# XIAO-HAT-3.net
KiCad netlist of a schematic drawn in Altium Designer
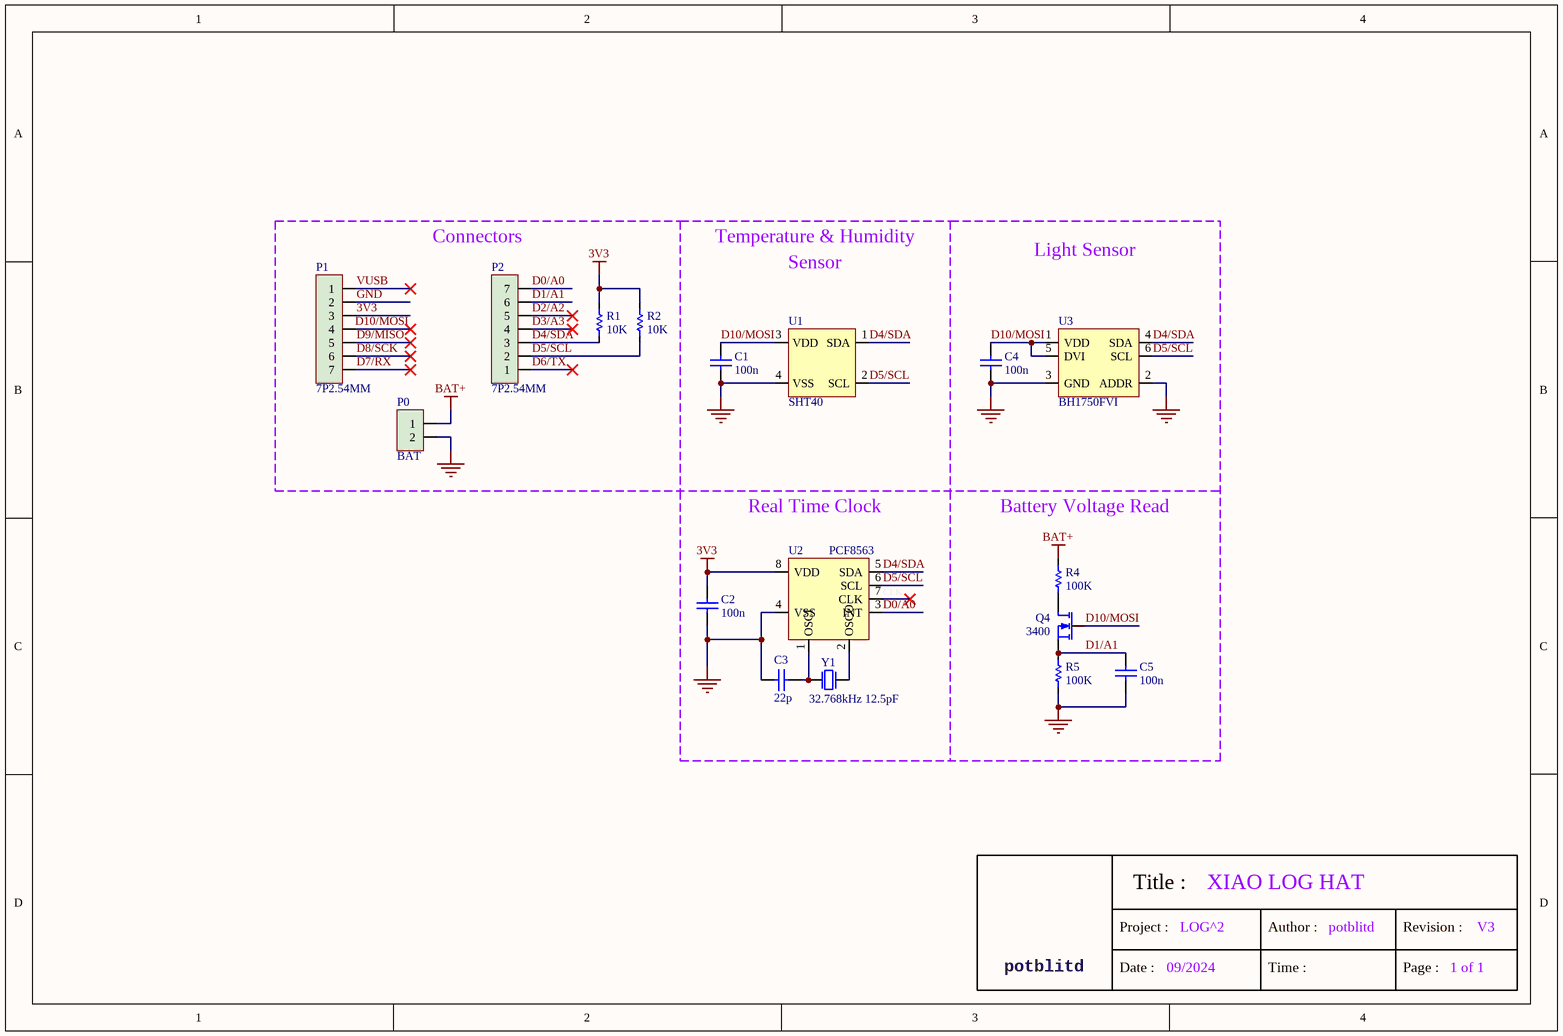
[diagram p0: XIAO-HAT-3.SchDoc]

(export (version "E")
  (design (tool "Eeschema 10.0.6"))
  (components
    (comp (ref "C1")
      (value "100n")
      (footprint "XIAO-HAT_0603C-BOX")
      (description "Capacitor 100nF ±10% 50V")
      (fields (field (name "MANUFACTURER") "Samsung") (field (name "Comment") "Capacitor"))
      (libsource (lib "Simulation Generic Components") (part "Capacitor"))
    )
    (comp (ref "C2")
      (value "100n")
      (footprint "XIAO-HAT_0603C-BOX")
      (description "Capacitor 100nF ±10% 50V")
      (fields (field (name "MANUFACTURER") "Samsung") (field (name "Comment") "Capacitor"))
      (libsource (lib "Simulation Generic Components") (part "Capacitor"))
    )
    (comp (ref "C3")
      (value "22p")
      (footprint "XIAO-HAT_0603C-BOX")
      (description "Capacitor 22pF ±5% 50V")
      (fields (field (name "MANUFACTURER") "Samsung") (field (name "Comment") "Capacitor"))
      (libsource (lib "Simulation Generic Components") (part "Capacitor"))
    )
    (comp (ref "C4")
      (value "100n")
      (footprint "XIAO-HAT_0603C-BOX")
      (description "Capacitor 100nF ±10% 50V")
      (fields (field (name "MANUFACTURER") "Samsung") (field (name "Comment") "Capacitor"))
      (libsource (lib "Simulation Generic Components") (part "Capacitor"))
    )
    (comp (ref "C5")
      (value "100n")
      (footprint "XIAO-HAT_0603C-BOX")
      (description "Capacitor 100nF ±10% 50V")
      (fields (field (name "MANUFACTURER") "Samsung") (field (name "Comment") "Capacitor"))
      (libsource (lib "Simulation Generic Components") (part "Capacitor"))
    )
    (comp (ref "P0")
      (value "BAT")
      (footprint "2P-2.54mm-NOSILK")
      (description "General 2-pin connection")
      (libsource (lib "AltiumLib") (part "2-pins Header"))
    )
    (comp (ref "P1")
      (value "7P2.54MM")
      (footprint "7P-2.54mm-XIAO")
      (description "General 7-pin connection")
      (libsource (lib "AltiumLib") (part "7-pins Header"))
    )
    (comp (ref "P2")
      (value "7P2.54MM")
      (footprint "7P-2.54mm-XIAO")
      (description "General 7-pin connection")
      (libsource (lib "") (part "7-pins Header_1"))
    )
    (comp (ref "Q4")
      (value "3400")
      (footprint "XIAO-HAT_SOT23-3")
      (description "MOSFET N-channel 30V 5.7A")
      (fields (field (name "MANUFACTURER") "UMW(友台半导体)"))
      (libsource (lib "AltiumLib") (part "MOSFET-N"))
    )
    (comp (ref "R1")
      (value "10K")
      (footprint "XIAO-HAT_0603R-BOX")
      (description "Resistor 10kΩ ±1% 1/16W")
      (fields (field (name "MANUFACTURER") "UNI-ROYAL(厚声)") (field (name "Comment") "Resistor"))
      (libsource (lib "Simulation Generic Components") (part "RES"))
    )
    (comp (ref "R2")
      (value "10K")
      (footprint "XIAO-HAT_0603R-BOX")
      (description "Resistor 10kΩ ±1% 1/16W")
      (fields (field (name "MANUFACTURER") "UNI-ROYAL(厚声)") (field (name "Comment") "Resistor"))
      (libsource (lib "Simulation Generic Components") (part "RES"))
    )
    (comp (ref "R4")
      (value "100K")
      (footprint "XIAO-HAT_0603R-BOX")
      (description "Resistor 100kΩ ±1% 100mW")
      (fields (field (name "MANUFACTURER") "UNI-ROYAL(厚声)") (field (name "Comment") "Resistor"))
      (libsource (lib "Simulation Generic Components") (part "RES"))
    )
    (comp (ref "R5")
      (value "100K")
      (footprint "XIAO-HAT_0603R-BOX")
      (description "Resistor 100kΩ ±1% 100mW")
      (fields (field (name "MANUFACTURER") "UNI-ROYAL(厚声)") (field (name "Comment") "Resistor"))
      (libsource (lib "Simulation Generic Components") (part "RES"))
    )
    (comp (ref "U1")
      (value "SHT40")
      (footprint "XIAO-HAT_SHT40")
      (description "SHT40 temperature and humidity sensor")
      (fields (field (name "MANUFACTURER") "Sensirion(瑞士盛思锐)"))
      (libsource (lib "AltiumLib") (part "SHT40"))
    )
    (comp (ref "U2")
      (value "PCF8563")
      (footprint "XIAO-HAT_SOP-8")
      (description "IC real-time clock with alarm interrupt")
      (fields (field (name "MANUFACTURER") "NXP"))
      (libsource (lib "AltiumLib") (part "RTC-8563"))
    )
    (comp (ref "U3")
      (value "BH1750FVI")
      (footprint "XIAO-HAT_BH1750")
      (description "Digital light sensor")
      (fields (field (name "MANUFACTURER") "ROHM"))
      (libsource (lib "AltiumLib") (part "BH1750"))
    )
    (comp (ref "Y1")
      (value "32.768kHz 12.5pF")
      (footprint "XIAO-HAT_FC135")
      (description "Crystal oscillator 32.768kHz 20ppm 12.5pF")
      (fields (field (name "MANUFACTURER") "TKD") (field (name "Comment") "Oscillator"))
      (libsource (lib "AltiumLib") (part "XO-2"))
    )
  )
  (nets
    (net (code "1") (name "/CLK") (class "Default")
      (node (ref "U2") (pin "7") (pinfunction "CLK_7") (pintype "passive+no_connect"))
    )
    (net (code "2") (name "/D0{slash}A0") (class "Default")
      (node (ref "P2") (pin "7") (pinfunction "7_7") (pintype "passive"))
      (node (ref "U2") (pin "3") (pinfunction "INT_3") (pintype "passive"))
    )
    (net (code "3") (name "/D1{slash}A1") (class "Default")
      (node (ref "C5") (pin "1") (pinfunction "1_1") (pintype "passive"))
      (node (ref "P2") (pin "6") (pinfunction "6_6") (pintype "passive"))
      (node (ref "Q4") (pin "2") (pinfunction "S_2") (pintype "passive"))
      (node (ref "R5") (pin "2") (pinfunction "2_2") (pintype "passive"))
    )
    (net (code "4") (name "/D2{slash}A2") (class "Default")
      (node (ref "P2") (pin "5") (pinfunction "5_5") (pintype "passive+no_connect"))
    )
    (net (code "5") (name "/D3{slash}A3") (class "Default")
      (node (ref "P2") (pin "4") (pinfunction "4_4") (pintype "passive+no_connect"))
    )
    (net (code "6") (name "/D4{slash}SDA") (class "Default")
      (node (ref "P2") (pin "3") (pinfunction "3_3") (pintype "passive"))
      (node (ref "R1") (pin "1") (pinfunction "1_1") (pintype "passive"))
      (node (ref "U1") (pin "1") (pinfunction "SDA_1") (pintype "passive"))
      (node (ref "U2") (pin "5") (pinfunction "SDA_5") (pintype "passive"))
      (node (ref "U3") (pin "4") (pinfunction "SDA_4") (pintype "passive"))
    )
    (net (code "7") (name "/D5{slash}SCL") (class "Default")
      (node (ref "P2") (pin "2") (pinfunction "2_2") (pintype "passive"))
      (node (ref "R2") (pin "1") (pinfunction "1_1") (pintype "passive"))
      (node (ref "U1") (pin "2") (pinfunction "SCL_2") (pintype "passive"))
      (node (ref "U2") (pin "6") (pinfunction "SCL_6") (pintype "passive"))
      (node (ref "U3") (pin "6") (pinfunction "SCL_6") (pintype "passive"))
    )
    (net (code "8") (name "/D6{slash}TX") (class "Default")
      (node (ref "P2") (pin "1") (pinfunction "1_1") (pintype "passive+no_connect"))
    )
    (net (code "9") (name "/D7{slash}RX") (class "Default")
      (node (ref "P1") (pin "7") (pinfunction "7_7") (pintype "passive+no_connect"))
    )
    (net (code "10") (name "/D8{slash}SCK") (class "Default")
      (node (ref "P1") (pin "6") (pinfunction "6_6") (pintype "passive+no_connect"))
    )
    (net (code "11") (name "/D9{slash}MISO") (class "Default")
      (node (ref "P1") (pin "5") (pinfunction "5_5") (pintype "passive+no_connect"))
    )
    (net (code "12") (name "/D10{slash}MOSI") (class "Default")
      (node (ref "C1") (pin "1") (pinfunction "1_1") (pintype "passive"))
      (node (ref "C4") (pin "1") (pinfunction "1_1") (pintype "passive"))
      (node (ref "P1") (pin "4") (pinfunction "4_4") (pintype "passive"))
      (node (ref "Q4") (pin "1") (pinfunction "G_1") (pintype "passive"))
      (node (ref "U1") (pin "3") (pinfunction "VDD_3") (pintype "passive"))
      (node (ref "U3") (pin "1") (pinfunction "VDD_1") (pintype "passive"))
      (node (ref "U3") (pin "5") (pinfunction "DVI_5") (pintype "passive"))
    )
    (net (code "13") (name "/VUSB") (class "Default")
      (node (ref "P1") (pin "1") (pinfunction "1_1") (pintype "passive+no_connect"))
    )
    (net (code "14") (name "3V3") (class "Default")
      (node (ref "C2") (pin "1") (pinfunction "1_1") (pintype "passive"))
      (node (ref "P1") (pin "3") (pinfunction "3_3") (pintype "passive"))
      (node (ref "R1") (pin "2") (pinfunction "2_2") (pintype "passive"))
      (node (ref "R2") (pin "2") (pinfunction "2_2") (pintype "passive"))
      (node (ref "U2") (pin "8") (pinfunction "VDD_8") (pintype "passive"))
    )
    (net (code "15") (name "BAT+") (class "Default")
      (node (ref "P0") (pin "1") (pinfunction "1_1") (pintype "passive"))
      (node (ref "R4") (pin "2") (pinfunction "2_2") (pintype "passive"))
    )
    (net (code "16") (name "GND") (class "Default")
      (node (ref "C1") (pin "2") (pinfunction "2_2") (pintype "passive"))
      (node (ref "C2") (pin "2") (pinfunction "2_2") (pintype "passive"))
      (node (ref "C3") (pin "2") (pinfunction "2_2") (pintype "passive"))
      (node (ref "C4") (pin "2") (pinfunction "2_2") (pintype "passive"))
      (node (ref "C5") (pin "2") (pinfunction "2_2") (pintype "passive"))
      (node (ref "P0") (pin "2") (pinfunction "2_2") (pintype "passive"))
      (node (ref "P1") (pin "2") (pinfunction "2_2") (pintype "passive"))
      (node (ref "R5") (pin "1") (pinfunction "1_1") (pintype "passive"))
      (node (ref "U1") (pin "4") (pinfunction "VSS_4") (pintype "passive"))
      (node (ref "U2") (pin "4") (pinfunction "VSS_4") (pintype "passive"))
      (node (ref "U3") (pin "2") (pinfunction "ADDR_2") (pintype "passive"))
      (node (ref "U3") (pin "3") (pinfunction "GND_3") (pintype "passive"))
    )
    (net (code "17") (name "Net-(Q4-D)") (class "Default")
      (node (ref "Q4") (pin "3") (pinfunction "D_3") (pintype "passive"))
      (node (ref "R4") (pin "1") (pinfunction "1_1") (pintype "passive"))
    )
    (net (code "18") (name "Net-(U2-OSCI)") (class "Default")
      (node (ref "C3") (pin "1") (pinfunction "1_1") (pintype "passive"))
      (node (ref "U2") (pin "1") (pinfunction "OSCI_1") (pintype "passive"))
      (node (ref "Y1") (pin "2") (pinfunction "2_2") (pintype "passive"))
    )
    (net (code "19") (name "Net-(U2-OSCO)") (class "Default")
      (node (ref "U2") (pin "2") (pinfunction "OSCO_2") (pintype "passive"))
      (node (ref "Y1") (pin "1") (pinfunction "1_1") (pintype "passive"))
    )
  )
)
